# MGMEZZ04_LoopBack.net
KiCad netlist of a schematic drawn in Altium Designer
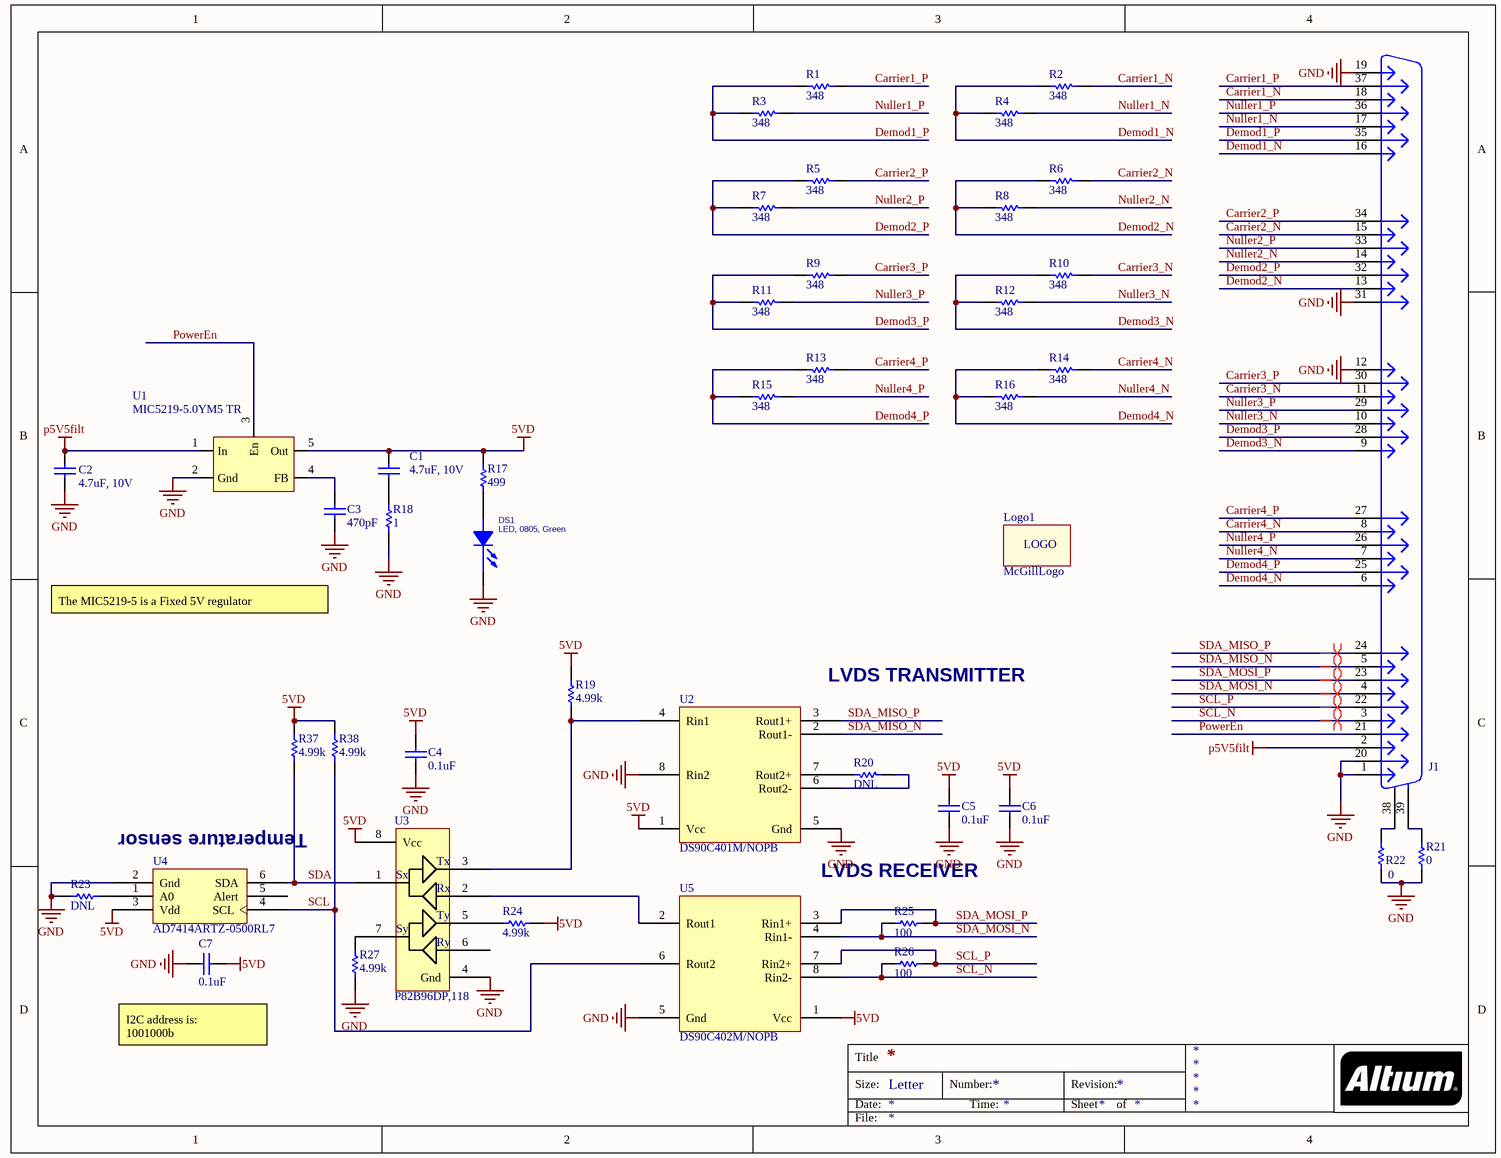
[diagram p0: MGMEZZ04_LoopBack.SchDoc]

(export (version "E")
  (design (tool "Eeschema 10.0.6"))
  (components
    (comp (ref "C1")
      (value "4.7uF, 10V")
      (footprint "0805")
      (description "4.7uF 10V Capacitor, Ceramic, 0805")
      (fields
        (field (name "MANUFACTURER") "Taiyo Yuden")
        (field (name "MANUFACTURER PART NUMBER") "LMK212BJ475KD-T")
      )
      (libsource (lib "MGMEZZ04") (part "CAP 0805"))
    )
    (comp (ref "C2")
      (value "4.7uF, 10V")
      (footprint "0805")
      (description "4.7uF 10V Capacitor, Ceramic, 0805")
      (fields
        (field (name "MANUFACTURER") "Taiyo Yuden")
        (field (name "MANUFACTURER PART NUMBER") "LMK212BJ475KD-T")
      )
      (libsource (lib "MGMEZZ04") (part "CAP 0805"))
    )
    (comp (ref "C3")
      (value "470pF")
      (footprint "0603")
      (description "470pF Capacitor, Ceramic, 0603")
      (fields
        (field (name "MANUFACTURER") "Kemet")
        (field (name "MANUFACTURER PART NUMBER") "C0603C471K5RACTU")
      )
      (libsource (lib "MiniSquidCtrl") (part "Cap0603"))
    )
    (comp (ref "C4")
      (value "0.1uF")
      (footprint "0603")
      (description "0.1uF 0603 Ceramic Capacitor")
      (fields
        (field (name "MANUFACTURER") "Kemet")
        (field (name "MANUFACTURER PART NUMBER") "C0603C104K4RACTU")
      )
      (libsource (lib "MiniSquidCtrl") (part "Cap0603"))
    )
    (comp (ref "C5")
      (value "0.1uF")
      (footprint "0603")
      (description "0.1uF 0603 Ceramic Capacitor")
      (fields
        (field (name "MANUFACTURER") "Kemet")
        (field (name "MANUFACTURER PART NUMBER") "C0603C104K4RACTU")
      )
      (libsource (lib "MiniSquidCtrl") (part "Cap0603"))
    )
    (comp (ref "C6")
      (value "0.1uF")
      (footprint "0603")
      (description "0.1uF 0603 Ceramic Capacitor")
      (fields
        (field (name "MANUFACTURER") "Kemet")
        (field (name "MANUFACTURER PART NUMBER") "C0603C104K4RACTU")
      )
      (libsource (lib "MiniSquidCtrl") (part "Cap0603"))
    )
    (comp (ref "C7")
      (value "0.1uF")
      (footprint "0603")
      (description "0.1uF 0603 Ceramic Capacitor")
      (fields
        (field (name "MANUFACTURER") "Kemet")
        (field (name "MANUFACTURER PART NUMBER") "C0603C104K4RACTU")
      )
      (libsource (lib "MiniSquidCtrl") (part "Cap0603"))
    )
    (comp (ref "DS1")
      (value "LED, 0805, Green")
      (description "LED GREEN CLEAR 0805 SMD")
      (fields
        (field (name "MANUFACTURER") "Lite-On Inc")
        (field (name "MANUFACTURER PART NUMBER") "LTST-C170GKT")
      )
      (libsource (lib "MGMEZZ04_Loopback") (part "LED"))
    )
    (comp (ref "J1")
      (value "DB37M")
      (footprint "DSUB37-M")
      (fields
        (field (name "MANUFACTURER") "Norcomp")
        (field (name "MANUFACTURER PART NUMBER") "182-037-113R531")
      )
      (libsource (lib "MGMEZZ04_Loopback") (part "DB37M"))
    )
    (comp (ref "Logo1")
      (value "McGillLogo")
      (footprint "McGillLogo1")
      (description "Silkscreen Logo")
      (fields (field (name "MANUFACTURER") "McGill"))
      (libsource (lib "MGMEZZ04_Loopback") (part "Logo"))
    )
    (comp (ref "R1")
      (value "348")
      (footprint "0603")
      (description "348 Ohm RES 0603")
      (fields
        (field (name "MANUFACTURER") "Vishay Dale")
        (field (name "MANUFACTURER PART NUMBER") "CRCW0603348RFKEA")
      )
      (libsource (lib "MiniSquidCtrl") (part "Res0603"))
    )
    (comp (ref "R2")
      (value "348")
      (footprint "0603")
      (description "348 Ohm RES 0603")
      (fields
        (field (name "MANUFACTURER") "Vishay Dale")
        (field (name "MANUFACTURER PART NUMBER") "CRCW0603348RFKEA")
      )
      (libsource (lib "MiniSquidCtrl") (part "Res0603"))
    )
    (comp (ref "R3")
      (value "348")
      (footprint "0603")
      (description "348 Ohm RES 0603")
      (fields
        (field (name "MANUFACTURER") "Vishay Dale")
        (field (name "MANUFACTURER PART NUMBER") "CRCW0603348RFKEA")
      )
      (libsource (lib "MiniSquidCtrl") (part "Res0603"))
    )
    (comp (ref "R4")
      (value "348")
      (footprint "0603")
      (description "348 Ohm RES 0603")
      (fields
        (field (name "MANUFACTURER") "Vishay Dale")
        (field (name "MANUFACTURER PART NUMBER") "CRCW0603348RFKEA")
      )
      (libsource (lib "MiniSquidCtrl") (part "Res0603"))
    )
    (comp (ref "R5")
      (value "348")
      (footprint "0603")
      (description "348 Ohm RES 0603")
      (fields
        (field (name "MANUFACTURER") "Vishay Dale")
        (field (name "MANUFACTURER PART NUMBER") "CRCW0603348RFKEA")
      )
      (libsource (lib "MiniSquidCtrl") (part "Res0603"))
    )
    (comp (ref "R6")
      (value "348")
      (footprint "0603")
      (description "348 Ohm RES 0603")
      (fields
        (field (name "MANUFACTURER") "Vishay Dale")
        (field (name "MANUFACTURER PART NUMBER") "CRCW0603348RFKEA")
      )
      (libsource (lib "MiniSquidCtrl") (part "Res0603"))
    )
    (comp (ref "R7")
      (value "348")
      (footprint "0603")
      (description "348 Ohm RES 0603")
      (fields
        (field (name "MANUFACTURER") "Vishay Dale")
        (field (name "MANUFACTURER PART NUMBER") "CRCW0603348RFKEA")
      )
      (libsource (lib "MiniSquidCtrl") (part "Res0603"))
    )
    (comp (ref "R8")
      (value "348")
      (footprint "0603")
      (description "348 Ohm RES 0603")
      (fields
        (field (name "MANUFACTURER") "Vishay Dale")
        (field (name "MANUFACTURER PART NUMBER") "CRCW0603348RFKEA")
      )
      (libsource (lib "MiniSquidCtrl") (part "Res0603"))
    )
    (comp (ref "R9")
      (value "348")
      (footprint "0603")
      (description "348 Ohm RES 0603")
      (fields
        (field (name "MANUFACTURER") "Vishay Dale")
        (field (name "MANUFACTURER PART NUMBER") "CRCW0603348RFKEA")
      )
      (libsource (lib "MiniSquidCtrl") (part "Res0603"))
    )
    (comp (ref "R10")
      (value "348")
      (footprint "0603")
      (description "348 Ohm RES 0603")
      (fields
        (field (name "MANUFACTURER") "Vishay Dale")
        (field (name "MANUFACTURER PART NUMBER") "CRCW0603348RFKEA")
      )
      (libsource (lib "MiniSquidCtrl") (part "Res0603"))
    )
    (comp (ref "R11")
      (value "348")
      (footprint "0603")
      (description "348 Ohm RES 0603")
      (fields
        (field (name "MANUFACTURER") "Vishay Dale")
        (field (name "MANUFACTURER PART NUMBER") "CRCW0603348RFKEA")
      )
      (libsource (lib "MiniSquidCtrl") (part "Res0603"))
    )
    (comp (ref "R12")
      (value "348")
      (footprint "0603")
      (description "348 Ohm RES 0603")
      (fields
        (field (name "MANUFACTURER") "Vishay Dale")
        (field (name "MANUFACTURER PART NUMBER") "CRCW0603348RFKEA")
      )
      (libsource (lib "MiniSquidCtrl") (part "Res0603"))
    )
    (comp (ref "R13")
      (value "348")
      (footprint "0603")
      (description "348 Ohm RES 0603")
      (fields
        (field (name "MANUFACTURER") "Vishay Dale")
        (field (name "MANUFACTURER PART NUMBER") "CRCW0603348RFKEA")
      )
      (libsource (lib "MiniSquidCtrl") (part "Res0603"))
    )
    (comp (ref "R14")
      (value "348")
      (footprint "0603")
      (description "348 Ohm RES 0603")
      (fields
        (field (name "MANUFACTURER") "Vishay Dale")
        (field (name "MANUFACTURER PART NUMBER") "CRCW0603348RFKEA")
      )
      (libsource (lib "MiniSquidCtrl") (part "Res0603"))
    )
    (comp (ref "R15")
      (value "348")
      (footprint "0603")
      (description "348 Ohm RES 0603")
      (fields
        (field (name "MANUFACTURER") "Vishay Dale")
        (field (name "MANUFACTURER PART NUMBER") "CRCW0603348RFKEA")
      )
      (libsource (lib "MiniSquidCtrl") (part "Res0603"))
    )
    (comp (ref "R16")
      (value "348")
      (footprint "0603")
      (description "348 Ohm RES 0603")
      (fields
        (field (name "MANUFACTURER") "Vishay Dale")
        (field (name "MANUFACTURER PART NUMBER") "CRCW0603348RFKEA")
      )
      (libsource (lib "MiniSquidCtrl") (part "Res0603"))
    )
    (comp (ref "R17")
      (value "499")
      (footprint "0603")
      (description "499 Ohm RES 0603")
      (fields
        (field (name "MANUFACTURER") "Vishay Dale")
        (field (name "MANUFACTURER PART NUMBER") "CRCW0603499RFKEA")
      )
      (libsource (lib "MiniSquidCtrl") (part "RES 0603"))
    )
    (comp (ref "R18")
      (value "1")
      (footprint "0603")
      (description "1 Ohm RES 0603")
      (fields
        (field (name "MANUFACTURER") "Vishay Dale")
        (field (name "MANUFACTURER PART NUMBER") "CRCW06031R00FKEA")
      )
      (libsource (lib "MiniSquidCtrl") (part "Res0603"))
    )
    (comp (ref "R19")
      (value "4.99k")
      (footprint "0603")
      (description "4.99k Ohm RES 0603")
      (fields
        (field (name "MANUFACTURER") "Vishay Dale")
        (field (name "MANUFACTURER PART NUMBER") "CRCW06034K99FKEA")
      )
      (libsource (lib "MiniSquidCtrl") (part "Res0603"))
    )
    (comp (ref "R20")
      (value "DNL")
      (footprint "0603")
      (description "DO NOT LOAD (DNS)")
      (fields (field (name "MANUFACTURER") "Generic"))
      (libsource (lib "MiniSquidCtrl") (part "Res0603"))
    )
    (comp (ref "R21")
      (value "0")
      (footprint "0603")
      (description "0 Ohm RES 0603")
      (fields
        (field (name "MANUFACTURER") "Vishay Dale")
        (field (name "MANUFACTURER PART NUMBER") "CRCW06030000Z0EA")
      )
      (libsource (lib "MiniSquidCtrl") (part "RES 0603"))
    )
    (comp (ref "R22")
      (value "0")
      (footprint "0603")
      (description "0 Ohm RES 0603")
      (fields
        (field (name "MANUFACTURER") "Vishay Dale")
        (field (name "MANUFACTURER PART NUMBER") "CRCW06030000Z0EA")
      )
      (libsource (lib "MiniSquidCtrl") (part "RES 0603"))
    )
    (comp (ref "R23")
      (value "DNL")
      (footprint "0603")
      (description "DO NOT LOAD (DNS)")
      (fields (field (name "MANUFACTURER") "Generic"))
      (libsource (lib "MiniSquidCtrl") (part "Res0603"))
    )
    (comp (ref "R24")
      (value "4.99k")
      (footprint "0603")
      (description "4.99k Ohm RES 0603")
      (fields
        (field (name "MANUFACTURER") "Vishay Dale")
        (field (name "MANUFACTURER PART NUMBER") "CRCW06034K99FKEA")
      )
      (libsource (lib "MiniSquidCtrl") (part "Res0603"))
    )
    (comp (ref "R25")
      (value "100")
      (footprint "0603")
      (description "100 Ohm RES 0603")
      (fields
        (field (name "MANUFACTURER") "Vishay Dale")
        (field (name "MANUFACTURER PART NUMBER") "CRCW0603100RFKEA")
      )
      (libsource (lib "MiniSquidCtrl") (part "RES 0603"))
    )
    (comp (ref "R26")
      (value "100")
      (footprint "0603")
      (description "100 Ohm RES 0603")
      (fields
        (field (name "MANUFACTURER") "Vishay Dale")
        (field (name "MANUFACTURER PART NUMBER") "CRCW0603100RFKEA")
      )
      (libsource (lib "MiniSquidCtrl") (part "RES 0603"))
    )
    (comp (ref "R27")
      (value "4.99k")
      (footprint "0603")
      (description "4.99k Ohm RES 0603")
      (fields
        (field (name "MANUFACTURER") "Vishay Dale")
        (field (name "MANUFACTURER PART NUMBER") "CRCW06034K99FKEA")
      )
      (libsource (lib "MiniSquidCtrl") (part "Res0603"))
    )
    (comp (ref "R37")
      (value "4.99k")
      (footprint "0603")
      (description "4.99k Ohm RES 0603")
      (fields
        (field (name "MANUFACTURER") "Vishay Dale")
        (field (name "MANUFACTURER PART NUMBER") "CRCW06034K99FKEA")
      )
      (libsource (lib "MiniSquidCtrl") (part "Res0603"))
    )
    (comp (ref "R38")
      (value "4.99k")
      (footprint "0603")
      (description "4.99k Ohm RES 0603")
      (fields
        (field (name "MANUFACTURER") "Vishay Dale")
        (field (name "MANUFACTURER PART NUMBER") "CRCW06034K99FKEA")
      )
      (libsource (lib "MiniSquidCtrl") (part "Res0603"))
    )
    (comp (ref "U1")
      (value "MIC5219-5.0YM5 TR")
      (footprint "SOT23-5")
      (description "Adjustable 30uVrms noise 400mA regulator")
      (fields (field (name "MANUFACTURER") "Micrel Inc"))
      (libsource (lib "MGMEZZ04") (part "TPS73601DBVR"))
    )
    (comp (ref "U2")
      (value "DS90C401M/NOPB")
      (footprint "SO8")
      (description "IC DRV LVDS DUAL DIFF SGNL 8SOIC")
      (fields
        (field (name "MANUFACTURER") "Texas Instruments")
        (field (name "MANUFACTURER PART NUMBER") "DS90C401MX/NOPB")
      )
      (libsource (lib "MiniSquidCtrl") (part "DS90C401M/NOPB"))
    )
    (comp (ref "U3")
      (value "P82B96DP,118")
      (footprint "MSOP8-P82B96")
      (description "IC DUAL BI-DIR BUS BUFFER 8-TSSOP")
      (libsource (lib "MiniSquidCtrl") (part "P82B96"))
    )
    (comp (ref "U4")
      (value "AD7414ARTZ-0500RL7")
      (footprint "SOT23-6")
      (description "Digital Temperature Sensor, 11-Bit, +/-2 Degree Accurate")
      (fields (field (name "MANUFACTURER") "Analog Devices"))
      (libsource (lib "MiniSquidCtrl") (part "AD7414ARTZ-0500RL7"))
    )
    (comp (ref "U5")
      (value "DS90C402M/NOPB")
      (footprint "SO8")
      (description "IC REC LVDS DUAL DIFF SGNL 8SOIC")
      (fields
        (field (name "MANUFACTURER") "Texas Instruments")
        (field (name "MANUFACTURER PART NUMBER") "DS90C402MX/NOPB")
      )
      (libsource (lib "MiniSquidCtrl") (part "DS90C402M/NOPB"))
    )
  )
  (nets
    (net (code "1") (name "/Carrier1_N") (class "Default")
      (node (ref "J1") (pin "18") (pinfunction "18_18") (pintype "passive"))
      (node (ref "R2") (pin "2") (pinfunction "2_2") (pintype "passive"))
    )
    (net (code "2") (name "/Carrier1_P") (class "Default")
      (node (ref "J1") (pin "37") (pinfunction "37_37") (pintype "passive"))
      (node (ref "R1") (pin "2") (pinfunction "2_2") (pintype "passive"))
    )
    (net (code "3") (name "/Carrier2_N") (class "Default")
      (node (ref "J1") (pin "15") (pinfunction "15_15") (pintype "passive"))
      (node (ref "R6") (pin "2") (pinfunction "2_2") (pintype "passive"))
    )
    (net (code "4") (name "/Carrier2_P") (class "Default")
      (node (ref "J1") (pin "34") (pinfunction "34_34") (pintype "passive"))
      (node (ref "R5") (pin "2") (pinfunction "2_2") (pintype "passive"))
    )
    (net (code "5") (name "/Carrier3_N") (class "Default")
      (node (ref "J1") (pin "11") (pinfunction "11_11") (pintype "passive"))
      (node (ref "R10") (pin "2") (pinfunction "2_2") (pintype "passive"))
    )
    (net (code "6") (name "/Carrier3_P") (class "Default")
      (node (ref "J1") (pin "30") (pinfunction "30_30") (pintype "passive"))
      (node (ref "R9") (pin "2") (pinfunction "2_2") (pintype "passive"))
    )
    (net (code "7") (name "/Carrier4_N") (class "Default")
      (node (ref "J1") (pin "8") (pinfunction "8_8") (pintype "passive"))
      (node (ref "R14") (pin "2") (pinfunction "2_2") (pintype "passive"))
    )
    (net (code "8") (name "/Carrier4_P") (class "Default")
      (node (ref "J1") (pin "27") (pinfunction "27_27") (pintype "passive"))
      (node (ref "R13") (pin "2") (pinfunction "2_2") (pintype "passive"))
    )
    (net (code "9") (name "/Demod1_N") (class "Default")
      (node (ref "J1") (pin "16") (pinfunction "16_16") (pintype "passive"))
      (node (ref "R2") (pin "1") (pinfunction "1_1") (pintype "passive"))
      (node (ref "R4") (pin "1") (pinfunction "1_1") (pintype "passive"))
    )
    (net (code "10") (name "/Demod1_P") (class "Default")
      (node (ref "J1") (pin "35") (pinfunction "35_35") (pintype "passive"))
      (node (ref "R1") (pin "1") (pinfunction "1_1") (pintype "passive"))
      (node (ref "R3") (pin "1") (pinfunction "1_1") (pintype "passive"))
    )
    (net (code "11") (name "/Demod2_N") (class "Default")
      (node (ref "J1") (pin "13") (pinfunction "13_13") (pintype "passive"))
      (node (ref "R6") (pin "1") (pinfunction "1_1") (pintype "passive"))
      (node (ref "R8") (pin "1") (pinfunction "1_1") (pintype "passive"))
    )
    (net (code "12") (name "/Demod2_P") (class "Default")
      (node (ref "J1") (pin "32") (pinfunction "32_32") (pintype "passive"))
      (node (ref "R5") (pin "1") (pinfunction "1_1") (pintype "passive"))
      (node (ref "R7") (pin "1") (pinfunction "1_1") (pintype "passive"))
    )
    (net (code "13") (name "/Demod3_N") (class "Default")
      (node (ref "J1") (pin "9") (pinfunction "9_9") (pintype "passive"))
      (node (ref "R10") (pin "1") (pinfunction "1_1") (pintype "passive"))
      (node (ref "R12") (pin "1") (pinfunction "1_1") (pintype "passive"))
    )
    (net (code "14") (name "/Demod3_P") (class "Default")
      (node (ref "J1") (pin "28") (pinfunction "28_28") (pintype "passive"))
      (node (ref "R11") (pin "1") (pinfunction "1_1") (pintype "passive"))
      (node (ref "R9") (pin "1") (pinfunction "1_1") (pintype "passive"))
    )
    (net (code "15") (name "/Demod4_N") (class "Default")
      (node (ref "J1") (pin "6") (pinfunction "6_6") (pintype "passive"))
      (node (ref "R14") (pin "1") (pinfunction "1_1") (pintype "passive"))
      (node (ref "R16") (pin "1") (pinfunction "1_1") (pintype "passive"))
    )
    (net (code "16") (name "/Demod4_P") (class "Default")
      (node (ref "J1") (pin "25") (pinfunction "25_25") (pintype "passive"))
      (node (ref "R13") (pin "1") (pinfunction "1_1") (pintype "passive"))
      (node (ref "R15") (pin "1") (pinfunction "1_1") (pintype "passive"))
    )
    (net (code "17") (name "/Nuller1_N") (class "Default")
      (node (ref "J1") (pin "17") (pinfunction "17_17") (pintype "passive"))
      (node (ref "R4") (pin "2") (pinfunction "2_2") (pintype "passive"))
    )
    (net (code "18") (name "/Nuller1_P") (class "Default")
      (node (ref "J1") (pin "36") (pinfunction "36_36") (pintype "passive"))
      (node (ref "R3") (pin "2") (pinfunction "2_2") (pintype "passive"))
    )
    (net (code "19") (name "/Nuller2_N") (class "Default")
      (node (ref "J1") (pin "14") (pinfunction "14_14") (pintype "passive"))
      (node (ref "R8") (pin "2") (pinfunction "2_2") (pintype "passive"))
    )
    (net (code "20") (name "/Nuller2_P") (class "Default")
      (node (ref "J1") (pin "33") (pinfunction "33_33") (pintype "passive"))
      (node (ref "R7") (pin "2") (pinfunction "2_2") (pintype "passive"))
    )
    (net (code "21") (name "/Nuller3_N") (class "Default")
      (node (ref "J1") (pin "10") (pinfunction "10_10") (pintype "passive"))
      (node (ref "R12") (pin "2") (pinfunction "2_2") (pintype "passive"))
    )
    (net (code "22") (name "/Nuller3_P") (class "Default")
      (node (ref "J1") (pin "29") (pinfunction "29_29") (pintype "passive"))
      (node (ref "R11") (pin "2") (pinfunction "2_2") (pintype "passive"))
    )
    (net (code "23") (name "/Nuller4_N") (class "Default")
      (node (ref "J1") (pin "7") (pinfunction "7_7") (pintype "passive"))
      (node (ref "R16") (pin "2") (pinfunction "2_2") (pintype "passive"))
    )
    (net (code "24") (name "/Nuller4_P") (class "Default")
      (node (ref "J1") (pin "26") (pinfunction "26_26") (pintype "passive"))
      (node (ref "R15") (pin "2") (pinfunction "2_2") (pintype "passive"))
    )
    (net (code "25") (name "/PowerEn") (class "Default")
      (node (ref "J1") (pin "21") (pinfunction "21_21") (pintype "passive"))
      (node (ref "U1") (pin "3") (pinfunction "En_3") (pintype "passive"))
    )
    (net (code "26") (name "/SCL") (class "Default")
      (node (ref "R38") (pin "1") (pinfunction "1_1") (pintype "passive"))
      (node (ref "U4") (pin "4") (pinfunction "SCL_4") (pintype "passive"))
      (node (ref "U5") (pin "6") (pinfunction "Rout2_6") (pintype "passive"))
    )
    (net (code "27") (name "/SCL_N") (class "Default")
      (node (ref "J1") (pin "3") (pinfunction "3_3") (pintype "passive"))
      (node (ref "R26") (pin "1") (pinfunction "1_1") (pintype "passive"))
      (node (ref "U5") (pin "8") (pinfunction "Rin2-_8") (pintype "passive"))
    )
    (net (code "28") (name "/SCL_P") (class "Default")
      (node (ref "J1") (pin "22") (pinfunction "22_22") (pintype "passive"))
      (node (ref "R26") (pin "2") (pinfunction "2_2") (pintype "passive"))
      (node (ref "U5") (pin "7") (pinfunction "Rin2+_7") (pintype "passive"))
    )
    (net (code "29") (name "/SDA") (class "Default")
      (node (ref "R37") (pin "1") (pinfunction "1_1") (pintype "passive"))
      (node (ref "U3") (pin "1") (pinfunction "Sx_1") (pintype "passive"))
      (node (ref "U4") (pin "6") (pinfunction "SDA_6") (pintype "passive"))
    )
    (net (code "30") (name "/SDA_MISO_N") (class "Default")
      (node (ref "J1") (pin "5") (pinfunction "5_5") (pintype "passive"))
      (node (ref "U2") (pin "2") (pinfunction "Rout1-_2") (pintype "passive"))
    )
    (net (code "31") (name "/SDA_MISO_P") (class "Default")
      (node (ref "J1") (pin "24") (pinfunction "24_24") (pintype "passive"))
      (node (ref "U2") (pin "3") (pinfunction "Rout1+_3") (pintype "passive"))
    )
    (net (code "32") (name "/SDA_MOSI_N") (class "Default")
      (node (ref "J1") (pin "4") (pinfunction "4_4") (pintype "passive"))
      (node (ref "R25") (pin "1") (pinfunction "1_1") (pintype "passive"))
      (node (ref "U5") (pin "4") (pinfunction "Rin1-_4") (pintype "passive"))
    )
    (net (code "33") (name "/SDA_MOSI_P") (class "Default")
      (node (ref "J1") (pin "23") (pinfunction "23_23") (pintype "passive"))
      (node (ref "R25") (pin "2") (pinfunction "2_2") (pintype "passive"))
      (node (ref "U5") (pin "3") (pinfunction "Rin1+_3") (pintype "passive"))
    )
    (net (code "34") (name "5VD") (class "Default")
      (node (ref "C1") (pin "2") (pinfunction "2_2") (pintype "passive"))
      (node (ref "C4") (pin "2") (pinfunction "2_2") (pintype "passive"))
      (node (ref "C5") (pin "2") (pinfunction "2_2") (pintype "passive"))
      (node (ref "C6") (pin "2") (pinfunction "2_2") (pintype "passive"))
      (node (ref "C7") (pin "2") (pinfunction "2_2") (pintype "passive"))
      (node (ref "R17") (pin "1") (pinfunction "1_1") (pintype "passive"))
      (node (ref "R19") (pin "2") (pinfunction "2_2") (pintype "passive"))
      (node (ref "R24") (pin "2") (pinfunction "2_2") (pintype "passive"))
      (node (ref "R37") (pin "2") (pinfunction "2_2") (pintype "passive"))
      (node (ref "R38") (pin "2") (pinfunction "2_2") (pintype "passive"))
      (node (ref "U1") (pin "5") (pinfunction "Out_5") (pintype "passive"))
      (node (ref "U2") (pin "1") (pinfunction "Vcc_1") (pintype "passive"))
      (node (ref "U3") (pin "8") (pinfunction "Vcc_8") (pintype "passive"))
      (node (ref "U4") (pin "3") (pinfunction "Vdd_3") (pintype "power_in"))
      (node (ref "U5") (pin "1") (pinfunction "Vcc_1") (pintype "passive"))
    )
    (net (code "35") (name "GND") (class "Default")
      (node (ref "C2") (pin "1") (pinfunction "1_1") (pintype "passive"))
      (node (ref "C3") (pin "1") (pinfunction "1_1") (pintype "passive"))
      (node (ref "C4") (pin "1") (pinfunction "1_1") (pintype "passive"))
      (node (ref "C5") (pin "1") (pinfunction "1_1") (pintype "passive"))
      (node (ref "C6") (pin "1") (pinfunction "1_1") (pintype "passive"))
      (node (ref "C7") (pin "1") (pinfunction "1_1") (pintype "passive"))
      (node (ref "DS1") (pin "2") (pinfunction "CATHODE_2") (pintype "passive"))
      (node (ref "J1") (pin "1") (pinfunction "1_1") (pintype "passive"))
      (node (ref "J1") (pin "12") (pinfunction "12_12") (pintype "passive"))
      (node (ref "J1") (pin "19") (pinfunction "19_19") (pintype "passive"))
      (node (ref "J1") (pin "20") (pinfunction "20_20") (pintype "passive"))
      (node (ref "J1") (pin "31") (pinfunction "31_31") (pintype "passive"))
      (node (ref "R18") (pin "1") (pinfunction "1_1") (pintype "passive"))
      (node (ref "R21") (pin "2") (pinfunction "2_2") (pintype "passive"))
      (node (ref "R22") (pin "1") (pinfunction "1_1") (pintype "passive"))
      (node (ref "R23") (pin "2") (pinfunction "2_2") (pintype "passive"))
      (node (ref "R27") (pin "1") (pinfunction "1_1") (pintype "passive"))
      (node (ref "U1") (pin "2") (pinfunction "Gnd_2") (pintype "passive"))
      (node (ref "U2") (pin "5") (pinfunction "Gnd_5") (pintype "passive"))
      (node (ref "U2") (pin "8") (pinfunction "Rin2_8") (pintype "passive"))
      (node (ref "U3") (pin "4") (pinfunction "Gnd_4") (pintype "passive"))
      (node (ref "U4") (pin "2") (pinfunction "Gnd_2") (pintype "passive"))
      (node (ref "U5") (pin "5") (pinfunction "Gnd_5") (pintype "passive"))
    )
    (net (code "36") (name "Net-(C1-Pad1)") (class "Default")
      (node (ref "C1") (pin "1") (pinfunction "1_1") (pintype "passive"))
      (node (ref "R18") (pin "2") (pinfunction "2_2") (pintype "passive"))
    )
    (net (code "37") (name "Net-(DS1-ANODE)") (class "Default")
      (node (ref "DS1") (pin "1") (pinfunction "ANODE_1") (pintype "passive"))
      (node (ref "R17") (pin "2") (pinfunction "2_2") (pintype "passive"))
    )
    (net (code "38") (name "Net-(J1-MH1)") (class "Default")
      (node (ref "J1") (pin "38") (pinfunction "MH1_38") (pintype "passive"))
      (node (ref "R22") (pin "2") (pinfunction "2_2") (pintype "passive"))
    )
    (net (code "39") (name "Net-(J1-MH2)") (class "Default")
      (node (ref "J1") (pin "39") (pinfunction "MH2_39") (pintype "passive"))
      (node (ref "R21") (pin "1") (pinfunction "1_1") (pintype "passive"))
    )
    (net (code "40") (name "Net-(U1-FB)") (class "Default")
      (node (ref "C3") (pin "2") (pinfunction "2_2") (pintype "passive"))
      (node (ref "U1") (pin "4") (pinfunction "FB_4") (pintype "passive"))
    )
    (net (code "41") (name "Net-(U2-Rin1)") (class "Default")
      (node (ref "R19") (pin "1") (pinfunction "1_1") (pintype "passive"))
      (node (ref "U2") (pin "4") (pinfunction "Rin1_4") (pintype "passive"))
      (node (ref "U3") (pin "3") (pinfunction "Tx_3") (pintype "passive"))
    )
    (net (code "42") (name "Net-(U2-Rout2+)") (class "Default")
      (node (ref "R20") (pin "2") (pinfunction "2_2") (pintype "passive"))
      (node (ref "U2") (pin "7") (pinfunction "Rout2+_7") (pintype "passive"))
    )
    (net (code "43") (name "Net-(U2-Rout2-)") (class "Default")
      (node (ref "R20") (pin "1") (pinfunction "1_1") (pintype "passive"))
      (node (ref "U2") (pin "6") (pinfunction "Rout2-_6") (pintype "passive"))
    )
    (net (code "44") (name "Net-(U3-Rx)") (class "Default")
      (node (ref "U3") (pin "2") (pinfunction "Rx_2") (pintype "passive"))
      (node (ref "U5") (pin "2") (pinfunction "Rout1_2") (pintype "passive"))
    )
    (net (code "45") (name "Net-(U3-Sy)") (class "Default")
      (node (ref "R27") (pin "2") (pinfunction "2_2") (pintype "passive"))
      (node (ref "U3") (pin "7") (pinfunction "Sy_7") (pintype "passive"))
    )
    (net (code "46") (name "Net-(U3-Ty)") (class "Default")
      (node (ref "R24") (pin "1") (pinfunction "1_1") (pintype "passive"))
      (node (ref "U3") (pin "5") (pinfunction "Ty_5") (pintype "passive"))
    )
    (net (code "47") (name "Net-(U4-A0)") (class "Default")
      (node (ref "R23") (pin "1") (pinfunction "1_1") (pintype "passive"))
      (node (ref "U4") (pin "1") (pinfunction "A0_1") (pintype "power_in"))
    )
    (net (code "48") (name "p5V5filt") (class "Default")
      (node (ref "C2") (pin "2") (pinfunction "2_2") (pintype "passive"))
      (node (ref "J1") (pin "2") (pinfunction "2_2") (pintype "passive"))
      (node (ref "U1") (pin "1") (pinfunction "In_1") (pintype "passive"))
    )
    (net (code "49") (name "unconnected-(U3-Ry-Pad6)") (class "Default")
      (node (ref "U3") (pin "6") (pinfunction "Ry_6") (pintype "passive"))
    )
    (net (code "50") (name "unconnected-(U4-Alert-Pad5)") (class "Default")
      (node (ref "U4") (pin "5") (pinfunction "Alert_5") (pintype "passive"))
    )
  )
)
